# NBMC_SCHEMATIC_wout_709.net
KiCad netlist of a schematic drawn in EAGLE
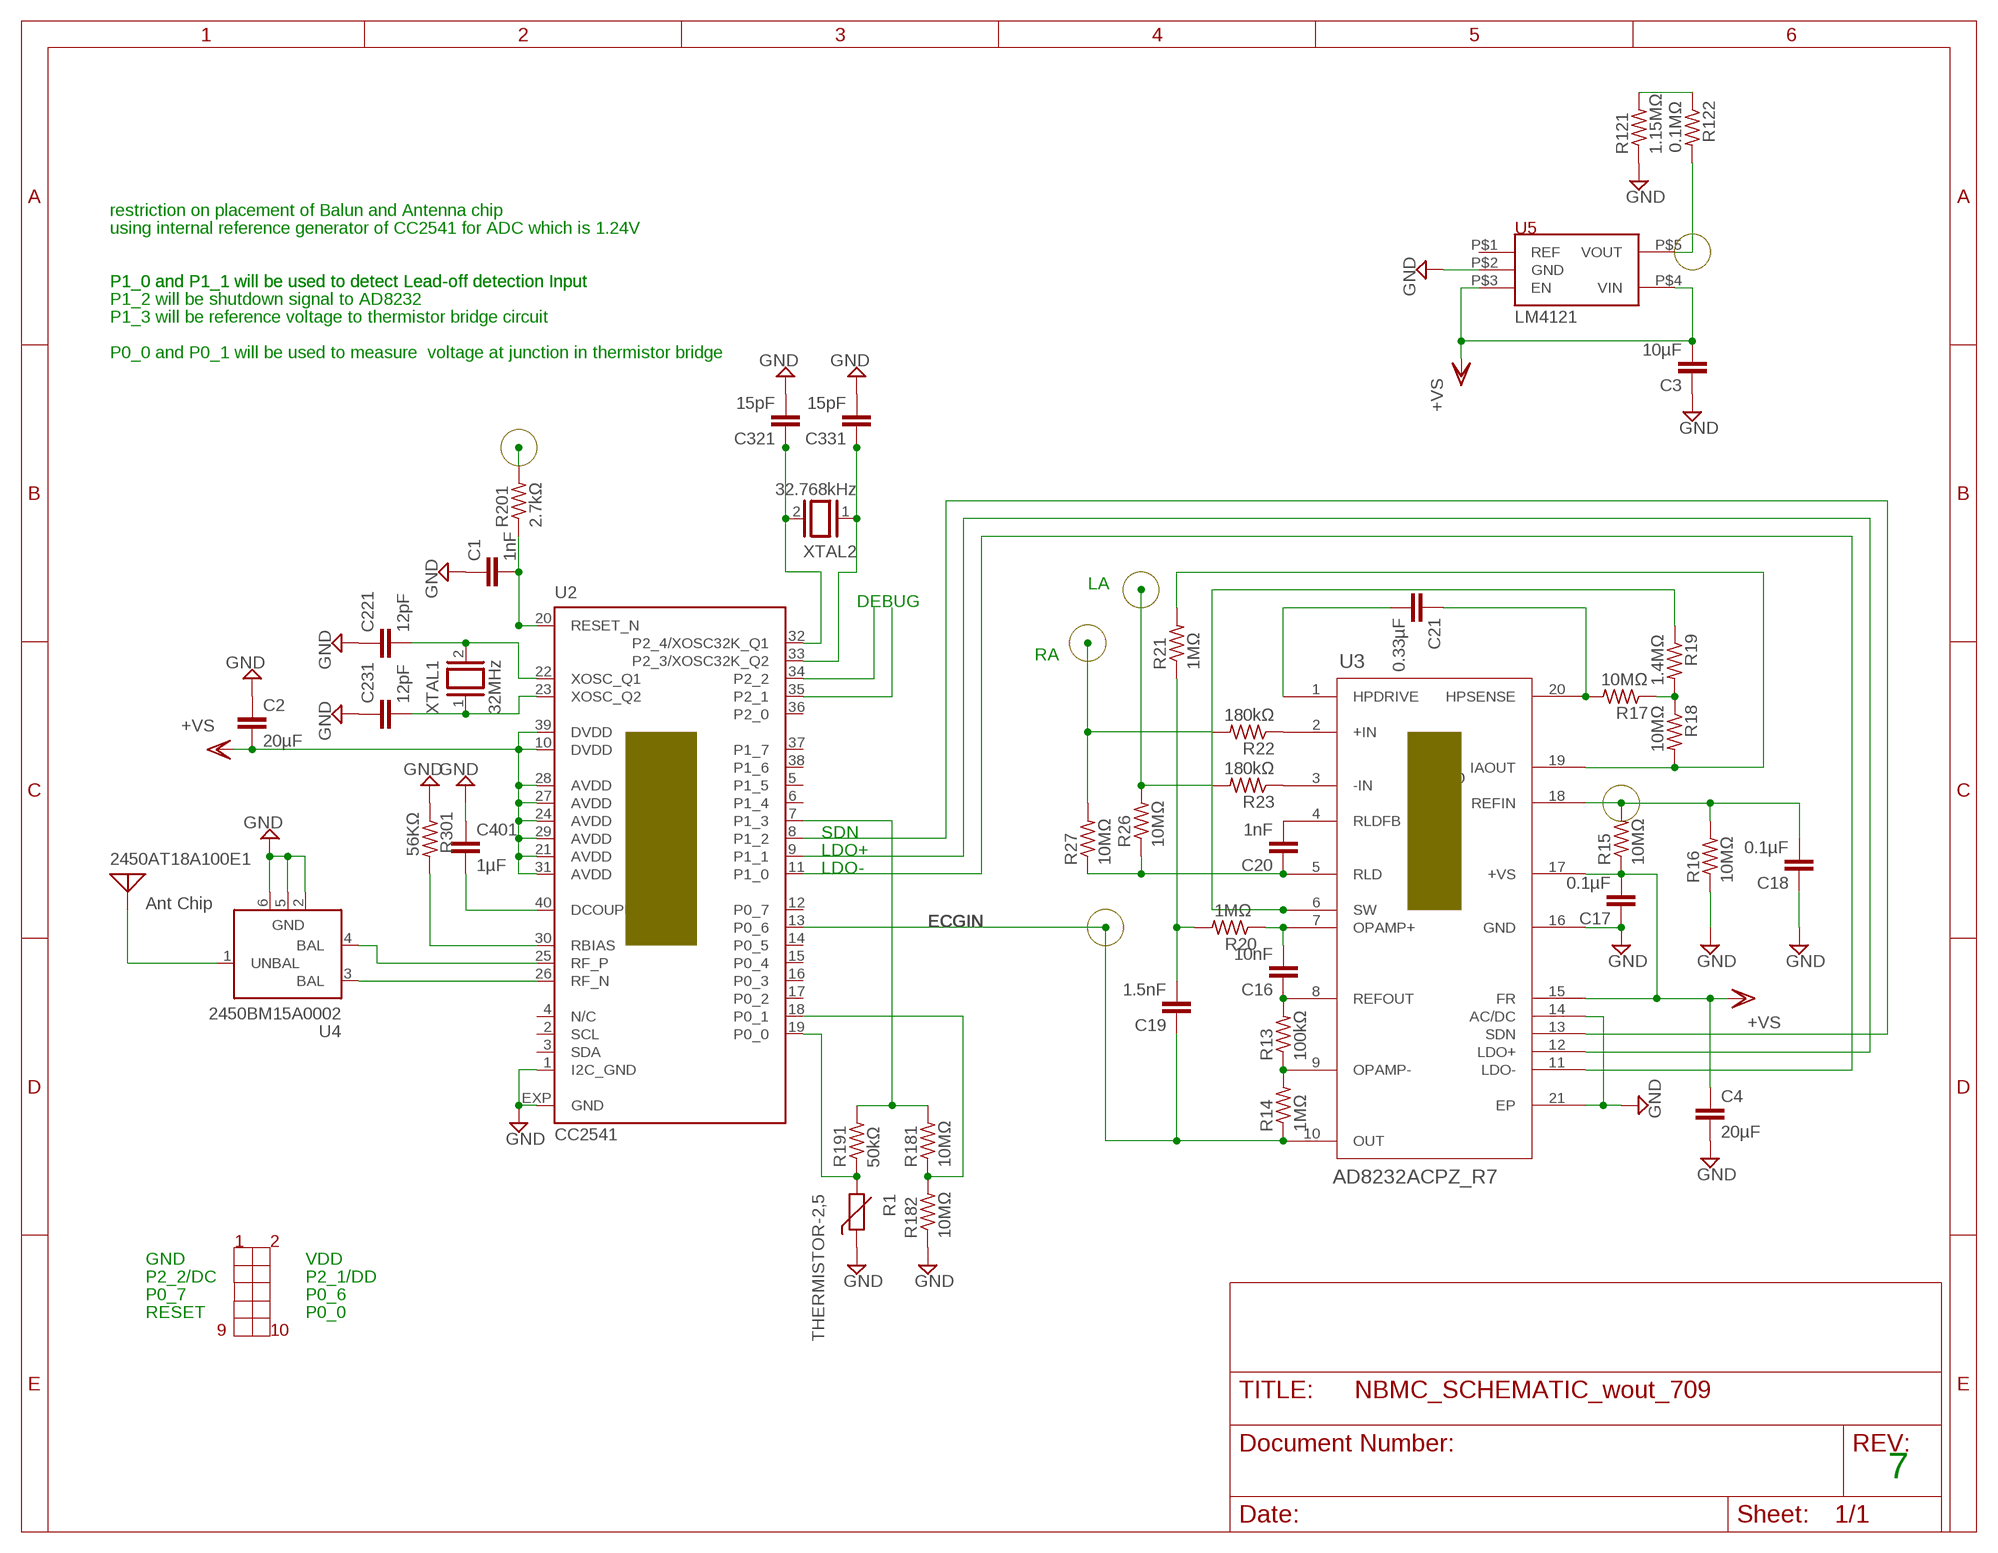
[diagram p0: schematic, sheet 1]

(export (version "E")
  (design (tool "Eeschema 10.0.6"))
  (components
    (comp (ref "2450AT18A100E1")
      (value "Ant Chip")
      (footprint "eagle-import:PAD-01")
      (libsource (lib "eagle-import") (part "ANTENNA"))
    )
    (comp (ref "C1")
      (value "1nF")
      (footprint "eagle-import:C0402")
      (libsource (lib "eagle-import") (part "C-EUC0402"))
    )
    (comp (ref "C2")
      (value "20µF")
      (footprint "eagle-import:C0402")
      (libsource (lib "eagle-import") (part "C-EUC0402"))
    )
    (comp (ref "C3")
      (value "10µF")
      (footprint "eagle-import:C0402")
      (libsource (lib "eagle-import") (part "C-EUC0402"))
    )
    (comp (ref "C4")
      (value "20µF")
      (footprint "eagle-import:C0402")
      (libsource (lib "eagle-import") (part "C-EUC0402"))
    )
    (comp (ref "C16")
      (value "10nF")
      (footprint "eagle-import:C0402")
      (libsource (lib "eagle-import") (part "C-EUC0402"))
    )
    (comp (ref "C17")
      (value "0.1µF")
      (footprint "eagle-import:C0402")
      (libsource (lib "eagle-import") (part "C-EUC0402"))
    )
    (comp (ref "C18")
      (value "0.1µF")
      (footprint "eagle-import:C0402")
      (libsource (lib "eagle-import") (part "C-EUC0402"))
    )
    (comp (ref "C19")
      (value "1.5nF")
      (footprint "eagle-import:C0402")
      (libsource (lib "eagle-import") (part "C-EUC0402"))
    )
    (comp (ref "C20")
      (value "1nF")
      (footprint "eagle-import:C0402")
      (libsource (lib "eagle-import") (part "C-EUC0402"))
    )
    (comp (ref "C21")
      (value "0.33µF")
      (footprint "eagle-import:C0402")
      (libsource (lib "eagle-import") (part "C-EUC0402"))
    )
    (comp (ref "C221")
      (value "12pF")
      (footprint "eagle-import:C0402")
      (libsource (lib "eagle-import") (part "C-EUC0402"))
    )
    (comp (ref "C231")
      (value "12pF")
      (footprint "eagle-import:C0402")
      (libsource (lib "eagle-import") (part "C-EUC0402"))
    )
    (comp (ref "C321")
      (value "15pF")
      (footprint "eagle-import:C0402")
      (libsource (lib "eagle-import") (part "C-EUC0402"))
    )
    (comp (ref "C331")
      (value "15pF")
      (footprint "eagle-import:C0402")
      (libsource (lib "eagle-import") (part "C-EUC0402"))
    )
    (comp (ref "C401")
      (value "1µF")
      (footprint "eagle-import:C0402")
      (libsource (lib "eagle-import") (part "C-EUC0402"))
    )
    (comp (ref "R1")
      (value "THERMISTOR-2,5")
      (footprint "eagle-import:RS-2,5")
      (libsource (lib "eagle-import") (part "THERMISTOR-2,5"))
    )
    (comp (ref "R13")
      (value "100kΩ")
      (footprint "eagle-import:R0402")
      (libsource (lib "eagle-import") (part "R-US_R0402"))
    )
    (comp (ref "R14")
      (value "1MΩ")
      (footprint "eagle-import:R0402")
      (libsource (lib "eagle-import") (part "R-US_R0402"))
    )
    (comp (ref "R15")
      (value "10MΩ")
      (footprint "eagle-import:R0402")
      (libsource (lib "eagle-import") (part "R-US_R0402"))
    )
    (comp (ref "R16")
      (value "10MΩ")
      (footprint "eagle-import:R0402")
      (libsource (lib "eagle-import") (part "R-US_R0402"))
    )
    (comp (ref "R17")
      (value "10MΩ")
      (footprint "eagle-import:R0402")
      (libsource (lib "eagle-import") (part "R-US_R0402"))
    )
    (comp (ref "R18")
      (value "10MΩ")
      (footprint "eagle-import:R0402")
      (libsource (lib "eagle-import") (part "R-US_R0402"))
    )
    (comp (ref "R19")
      (value "1.4MΩ")
      (footprint "eagle-import:R0402")
      (libsource (lib "eagle-import") (part "R-US_R0402"))
    )
    (comp (ref "R20")
      (value "1MΩ")
      (footprint "eagle-import:R0402")
      (libsource (lib "eagle-import") (part "R-US_R0402"))
    )
    (comp (ref "R21")
      (value "1MΩ")
      (footprint "eagle-import:R0402")
      (libsource (lib "eagle-import") (part "R-US_R0402"))
    )
    (comp (ref "R22")
      (value "180kΩ")
      (footprint "eagle-import:R0402")
      (libsource (lib "eagle-import") (part "R-US_R0402"))
    )
    (comp (ref "R23")
      (value "180kΩ")
      (footprint "eagle-import:R0402")
      (libsource (lib "eagle-import") (part "R-US_R0402"))
    )
    (comp (ref "R26")
      (value "10MΩ")
      (footprint "eagle-import:R0402")
      (libsource (lib "eagle-import") (part "R-US_R0402"))
    )
    (comp (ref "R27")
      (value "10MΩ")
      (footprint "eagle-import:R0402")
      (libsource (lib "eagle-import") (part "R-US_R0402"))
    )
    (comp (ref "R121")
      (value "1.15MΩ")
      (footprint "eagle-import:R0402")
      (libsource (lib "eagle-import") (part "R-US_R0402"))
    )
    (comp (ref "R122")
      (value "0.1MΩ")
      (footprint "eagle-import:R0402")
      (libsource (lib "eagle-import") (part "R-US_R0402"))
    )
    (comp (ref "R181")
      (value "10MΩ")
      (footprint "eagle-import:R0402")
      (libsource (lib "eagle-import") (part "R-US_R0402"))
    )
    (comp (ref "R182")
      (value "10MΩ")
      (footprint "eagle-import:R0402")
      (libsource (lib "eagle-import") (part "R-US_R0402"))
    )
    (comp (ref "R191")
      (value "50kΩ")
      (footprint "eagle-import:R0402")
      (libsource (lib "eagle-import") (part "R-US_R0402"))
    )
    (comp (ref "R201")
      (value "2.7kΩ")
      (footprint "eagle-import:R0402")
      (libsource (lib "eagle-import") (part "R-US_R0402"))
    )
    (comp (ref "R301")
      (value "56KΩ")
      (footprint "eagle-import:R0402")
      (libsource (lib "eagle-import") (part "R-US_R0402"))
    )
    (comp (ref "U2")
      (value "CC2541")
      (footprint "eagle-import:RHA_S-PVQFN-N40")
      (libsource (lib "eagle-import") (part "CC2541"))
    )
    (comp (ref "U3")
      (value "AD8232ACPZ_R7")
      (footprint "eagle-import:CP_20_10")
      (libsource (lib "eagle-import") (part "AD8232ACPZ_R7"))
    )
    (comp (ref "U4")
      (value "2450BM15A0002")
      (footprint "eagle-import:2450BM15A0002")
      (libsource (lib "eagle-import") (part "2450BM15A0002"))
    )
    (comp (ref "U5")
      (value "LM4121")
      (footprint "eagle-import:0402")
      (libsource (lib "eagle-import") (part "LM4121"))
    )
    (comp (ref "XTAL1")
      (value "32MHz")
      (footprint "eagle-import:Q")
      (libsource (lib "eagle-import") (part "XTAL"))
    )
    (comp (ref "XTAL2")
      (value "32.768kHz")
      (footprint "eagle-import:Q")
      (libsource (lib "eagle-import") (part "XTAL"))
    )
  )
  (nets
    (net (code "1") (name "+VS") (class "Default")
      (node (ref "C17") (pin "2") (pinfunction "2_2") (pintype "passive"))
      (node (ref "C2") (pin "2") (pinfunction "2_2") (pintype "passive"))
      (node (ref "C3") (pin "2") (pinfunction "2_2") (pintype "passive"))
      (node (ref "C4") (pin "1") (pinfunction "1_1") (pintype "passive"))
      (node (ref "R15") (pin "1") (pinfunction "1_1") (pintype "passive"))
      (node (ref "U2") (pin "10") (pinfunction "DVDD_10") (pintype "power_in"))
      (node (ref "U2") (pin "21") (pinfunction "AVDD_21") (pintype "power_in"))
      (node (ref "U2") (pin "24") (pinfunction "AVDD_24") (pintype "power_in"))
      (node (ref "U2") (pin "27") (pinfunction "AVDD_27") (pintype "power_in"))
      (node (ref "U2") (pin "28") (pinfunction "AVDD_28") (pintype "power_in"))
      (node (ref "U2") (pin "29") (pinfunction "AVDD_29") (pintype "power_in"))
      (node (ref "U2") (pin "31") (pinfunction "AVDD_31") (pintype "power_in"))
      (node (ref "U2") (pin "39") (pinfunction "DVDD_39") (pintype "power_in"))
      (node (ref "U3") (pin "15") (pinfunction "FR_15") (pintype "passive"))
      (node (ref "U3") (pin "17") (pinfunction "+VS_17") (pintype "passive"))
      (node (ref "U5") (pin "P$3") (pinfunction "EN_P$3") (pintype "input"))
      (node (ref "U5") (pin "P$4") (pinfunction "VIN_P$4") (pintype "input"))
    )
    (net (code "2") (name "/ECGIN") (class "Default")
      (node (ref "C19") (pin "1") (pinfunction "1_1") (pintype "passive"))
      (node (ref "R14") (pin "1") (pinfunction "1_1") (pintype "passive"))
      (node (ref "U2") (pin "13") (pinfunction "P0_6_13") (pintype "bidirectional"))
      (node (ref "U3") (pin "10") (pinfunction "OUT_10") (pintype "passive"))
    )
    (net (code "3") (name "/N{slash}C") (class "Default")
      (node (ref "U2") (pin "4") (pinfunction "N/C_4") (pintype "power_in"))
    )
    (net (code "4") (name "GND") (class "Default")
      (node (ref "C1") (pin "1") (pinfunction "1_1") (pintype "passive"))
      (node (ref "C17") (pin "1") (pinfunction "1_1") (pintype "passive"))
      (node (ref "C18") (pin "1") (pinfunction "1_1") (pintype "passive"))
      (node (ref "C2") (pin "1") (pinfunction "1_1") (pintype "passive"))
      (node (ref "C221") (pin "1") (pinfunction "1_1") (pintype "passive"))
      (node (ref "C231") (pin "1") (pinfunction "1_1") (pintype "passive"))
      (node (ref "C3") (pin "1") (pinfunction "1_1") (pintype "passive"))
      (node (ref "C321") (pin "2") (pinfunction "2_2") (pintype "passive"))
      (node (ref "C331") (pin "2") (pinfunction "2_2") (pintype "passive"))
      (node (ref "C4") (pin "2") (pinfunction "2_2") (pintype "passive"))
      (node (ref "C401") (pin "1") (pinfunction "1_1") (pintype "passive"))
      (node (ref "R1") (pin "1") (pinfunction "1_1") (pintype "passive"))
      (node (ref "R121") (pin "1") (pinfunction "1_1") (pintype "passive"))
      (node (ref "R16") (pin "1") (pinfunction "1_1") (pintype "passive"))
      (node (ref "R182") (pin "1") (pinfunction "1_1") (pintype "passive"))
      (node (ref "R301") (pin "1") (pinfunction "1_1") (pintype "passive"))
      (node (ref "U2") (pin "1") (pinfunction "I2C_GND_1") (pintype "power_in"))
      (node (ref "U2") (pin "EXP") (pinfunction "GND_EXP") (pintype "passive"))
      (node (ref "U3") (pin "14") (pinfunction "AC/DC_14") (pintype "passive"))
      (node (ref "U3") (pin "16") (pinfunction "GND_16") (pintype "passive"))
      (node (ref "U3") (pin "21") (pinfunction "EP_21") (pintype "passive"))
      (node (ref "U4") (pin "2") (pinfunction "GND_2") (pintype "passive"))
      (node (ref "U4") (pin "5") (pinfunction "GND_5") (pintype "passive"))
      (node (ref "U4") (pin "6") (pinfunction "GND_6") (pintype "passive"))
      (node (ref "U5") (pin "P$2") (pinfunction "GND_P$2") (pintype "bidirectional"))
    )
    (net (code "5") (name "Net-(C19-Pad2)") (class "Default")
      (node (ref "C19") (pin "2") (pinfunction "2_2") (pintype "passive"))
      (node (ref "R20") (pin "2") (pinfunction "2_2") (pintype "passive"))
      (node (ref "R21") (pin "1") (pinfunction "1_1") (pintype "passive"))
    )
    (net (code "6") (name "Net-(R17-Pad1)") (class "Default")
      (node (ref "R17") (pin "1") (pinfunction "1_1") (pintype "passive"))
      (node (ref "R18") (pin "1") (pinfunction "1_1") (pintype "passive"))
      (node (ref "R19") (pin "2") (pinfunction "2_2") (pintype "passive"))
    )
    (net (code "7") (name "Net-(R22-Pad2)") (class "Default")
      (node (ref "R22") (pin "2") (pinfunction "2_2") (pintype "passive"))
      (node (ref "R27") (pin "2") (pinfunction "2_2") (pintype "passive"))
    )
    (net (code "8") (name "Net-(R23-Pad2)") (class "Default")
      (node (ref "R23") (pin "2") (pinfunction "2_2") (pintype "passive"))
      (node (ref "R26") (pin "2") (pinfunction "2_2") (pintype "passive"))
    )
    (net (code "9") (name "Net-(R121-Pad2)") (class "Default")
      (node (ref "R121") (pin "2") (pinfunction "2_2") (pintype "passive"))
      (node (ref "R122") (pin "1") (pinfunction "1_1") (pintype "passive"))
    )
    (net (code "10") (name "Net-(U2-DCOUPL)") (class "Default")
      (node (ref "C401") (pin "2") (pinfunction "2_2") (pintype "passive"))
      (node (ref "U2") (pin "40") (pinfunction "DCOUPL_40") (pintype "power_in"))
    )
    (net (code "11") (name "Net-(U2-P0_0)") (class "Default")
      (node (ref "R1") (pin "2") (pinfunction "2_2") (pintype "passive"))
      (node (ref "R191") (pin "1") (pinfunction "1_1") (pintype "passive"))
      (node (ref "U2") (pin "19") (pinfunction "P0_0_19") (pintype "bidirectional"))
    )
    (net (code "12") (name "Net-(U2-P0_1)") (class "Default")
      (node (ref "R181") (pin "1") (pinfunction "1_1") (pintype "passive"))
      (node (ref "R182") (pin "2") (pinfunction "2_2") (pintype "passive"))
      (node (ref "U2") (pin "18") (pinfunction "P0_1_18") (pintype "bidirectional"))
    )
    (net (code "13") (name "Net-(U2-P1_0)") (class "Default")
      (node (ref "U2") (pin "11") (pinfunction "P1_0_11") (pintype "bidirectional"))
      (node (ref "U3") (pin "11") (pinfunction "LDO-_11") (pintype "passive"))
    )
    (net (code "14") (name "Net-(U2-P1_1)") (class "Default")
      (node (ref "U2") (pin "9") (pinfunction "P1_1_9") (pintype "bidirectional"))
      (node (ref "U3") (pin "12") (pinfunction "LDO+_12") (pintype "passive"))
    )
    (net (code "15") (name "Net-(U2-P1_2)") (class "Default")
      (node (ref "U2") (pin "8") (pinfunction "P1_2_8") (pintype "bidirectional"))
      (node (ref "U3") (pin "13") (pinfunction "SDN_13") (pintype "passive"))
    )
    (net (code "16") (name "Net-(U2-P1_3)") (class "Default")
      (node (ref "R181") (pin "2") (pinfunction "2_2") (pintype "passive"))
      (node (ref "R191") (pin "2") (pinfunction "2_2") (pintype "passive"))
      (node (ref "U2") (pin "7") (pinfunction "P1_3_7") (pintype "bidirectional"))
    )
    (net (code "17") (name "Net-(U2-P2_3{slash}XOSC32K_Q2)") (class "Default")
      (node (ref "C331") (pin "1") (pinfunction "1_1") (pintype "passive"))
      (node (ref "U2") (pin "33") (pinfunction "P2_3/XOSC32K_Q2_33") (pintype "bidirectional"))
      (node (ref "XTAL2") (pin "1") (pinfunction "1_1") (pintype "passive"))
    )
    (net (code "18") (name "Net-(U2-P2_4{slash}XOSC32K_Q1)") (class "Default")
      (node (ref "C321") (pin "1") (pinfunction "1_1") (pintype "passive"))
      (node (ref "U2") (pin "32") (pinfunction "P2_4/XOSC32K_Q1_32") (pintype "bidirectional"))
      (node (ref "XTAL2") (pin "2") (pinfunction "2_2") (pintype "passive"))
    )
    (net (code "19") (name "Net-(U2-RBIAS)") (class "Default")
      (node (ref "R301") (pin "2") (pinfunction "2_2") (pintype "passive"))
      (node (ref "U2") (pin "30") (pinfunction "RBIAS_30") (pintype "bidirectional"))
    )
    (net (code "20") (name "Net-(U2-RESET_N)") (class "Default")
      (node (ref "C1") (pin "2") (pinfunction "2_2") (pintype "passive"))
      (node (ref "R201") (pin "1") (pinfunction "1_1") (pintype "passive"))
      (node (ref "U2") (pin "20") (pinfunction "RESET_N_20") (pintype "input"))
    )
    (net (code "21") (name "Net-(U2-RF_N)") (class "Default")
      (node (ref "U2") (pin "26") (pinfunction "RF_N_26") (pintype "bidirectional"))
      (node (ref "U4") (pin "3") (pinfunction "BAL_3") (pintype "passive"))
    )
    (net (code "22") (name "Net-(U2-RF_P)") (class "Default")
      (node (ref "U2") (pin "25") (pinfunction "RF_P_25") (pintype "bidirectional"))
      (node (ref "U4") (pin "4") (pinfunction "BAL_4") (pintype "passive"))
    )
    (net (code "23") (name "Net-(U2-XOSC_Q1)") (class "Default")
      (node (ref "C221") (pin "2") (pinfunction "2_2") (pintype "passive"))
      (node (ref "U2") (pin "22") (pinfunction "XOSC_Q1_22") (pintype "bidirectional"))
      (node (ref "XTAL1") (pin "2") (pinfunction "2_2") (pintype "passive"))
    )
    (net (code "24") (name "Net-(U2-XOSC_Q2)") (class "Default")
      (node (ref "C231") (pin "2") (pinfunction "2_2") (pintype "passive"))
      (node (ref "U2") (pin "23") (pinfunction "XOSC_Q2_23") (pintype "bidirectional"))
      (node (ref "XTAL1") (pin "1") (pinfunction "1_1") (pintype "passive"))
    )
    (net (code "25") (name "Net-(U3-+IN)") (class "Default")
      (node (ref "R22") (pin "1") (pinfunction "1_1") (pintype "passive"))
      (node (ref "U3") (pin "2") (pinfunction "+IN_2") (pintype "passive"))
    )
    (net (code "26") (name "Net-(U3--IN)") (class "Default")
      (node (ref "R23") (pin "1") (pinfunction "1_1") (pintype "passive"))
      (node (ref "U3") (pin "3") (pinfunction "-IN_3") (pintype "passive"))
    )
    (net (code "27") (name "Net-(U3-HPDRIVE)") (class "Default")
      (node (ref "C21") (pin "2") (pinfunction "2_2") (pintype "passive"))
      (node (ref "U3") (pin "1") (pinfunction "HPDRIVE_1") (pintype "passive"))
    )
    (net (code "28") (name "Net-(U3-HPSENSE)") (class "Default")
      (node (ref "C21") (pin "1") (pinfunction "1_1") (pintype "passive"))
      (node (ref "R17") (pin "2") (pinfunction "2_2") (pintype "passive"))
      (node (ref "U3") (pin "20") (pinfunction "HPSENSE_20") (pintype "passive"))
    )
    (net (code "29") (name "Net-(U3-IAOUT)") (class "Default")
      (node (ref "R18") (pin "2") (pinfunction "2_2") (pintype "passive"))
      (node (ref "R21") (pin "2") (pinfunction "2_2") (pintype "passive"))
      (node (ref "U3") (pin "19") (pinfunction "IAOUT_19") (pintype "passive"))
    )
    (net (code "30") (name "Net-(U3-OPAMP+)") (class "Default")
      (node (ref "C16") (pin "2") (pinfunction "2_2") (pintype "passive"))
      (node (ref "R20") (pin "1") (pinfunction "1_1") (pintype "passive"))
      (node (ref "U3") (pin "7") (pinfunction "OPAMP+_7") (pintype "passive"))
    )
    (net (code "31") (name "Net-(U3-OPAMP-)") (class "Default")
      (node (ref "R13") (pin "1") (pinfunction "1_1") (pintype "passive"))
      (node (ref "R14") (pin "2") (pinfunction "2_2") (pintype "passive"))
      (node (ref "U3") (pin "9") (pinfunction "OPAMP-_9") (pintype "passive"))
    )
    (net (code "32") (name "Net-(U3-REFIN)") (class "Default")
      (node (ref "C18") (pin "2") (pinfunction "2_2") (pintype "passive"))
      (node (ref "R15") (pin "2") (pinfunction "2_2") (pintype "passive"))
      (node (ref "R16") (pin "2") (pinfunction "2_2") (pintype "passive"))
      (node (ref "U3") (pin "18") (pinfunction "REFIN_18") (pintype "passive"))
    )
    (net (code "33") (name "Net-(U3-REFOUT)") (class "Default")
      (node (ref "C16") (pin "1") (pinfunction "1_1") (pintype "passive"))
      (node (ref "R13") (pin "2") (pinfunction "2_2") (pintype "passive"))
      (node (ref "U3") (pin "8") (pinfunction "REFOUT_8") (pintype "passive"))
    )
    (net (code "34") (name "Net-(U3-RLD)") (class "Default")
      (node (ref "C20") (pin "1") (pinfunction "1_1") (pintype "passive"))
      (node (ref "R26") (pin "1") (pinfunction "1_1") (pintype "passive"))
      (node (ref "R27") (pin "1") (pinfunction "1_1") (pintype "passive"))
      (node (ref "U3") (pin "5") (pinfunction "RLD_5") (pintype "passive"))
    )
    (net (code "35") (name "Net-(U3-RLDFB)") (class "Default")
      (node (ref "C20") (pin "2") (pinfunction "2_2") (pintype "passive"))
      (node (ref "U3") (pin "4") (pinfunction "RLDFB_4") (pintype "passive"))
    )
    (net (code "36") (name "Net-(U3-SW)") (class "Default")
      (node (ref "R19") (pin "1") (pinfunction "1_1") (pintype "passive"))
      (node (ref "U3") (pin "6") (pinfunction "SW_6") (pintype "passive"))
    )
    (net (code "37") (name "Net-(U4-UNBAL)") (class "Default")
      (node (ref "2450AT18A100E1") (pin "1") (pinfunction "1_1") (pintype "output"))
      (node (ref "U4") (pin "1") (pinfunction "UNBAL_1") (pintype "passive"))
    )
    (net (code "38") (name "Net-(U5-VOUT)") (class "Default")
      (node (ref "R122") (pin "2") (pinfunction "2_2") (pintype "passive"))
      (node (ref "U5") (pin "P$5") (pinfunction "VOUT_P$5") (pintype "output"))
    )
    (net (code "39") (name "unconnected-(R201-Pad2)") (class "Default")
      (node (ref "R201") (pin "2") (pinfunction "2_2") (pintype "passive"))
    )
    (net (code "40") (name "unconnected-(U2-P0_2-Pad17)") (class "Default")
      (node (ref "U2") (pin "17") (pinfunction "P0_2_17") (pintype "bidirectional"))
    )
    (net (code "41") (name "unconnected-(U2-P0_3-Pad16)") (class "Default")
      (node (ref "U2") (pin "16") (pinfunction "P0_3_16") (pintype "bidirectional"))
    )
    (net (code "42") (name "unconnected-(U2-P0_4-Pad15)") (class "Default")
      (node (ref "U2") (pin "15") (pinfunction "P0_4_15") (pintype "bidirectional"))
    )
    (net (code "43") (name "unconnected-(U2-P0_5-Pad14)") (class "Default")
      (node (ref "U2") (pin "14") (pinfunction "P0_5_14") (pintype "bidirectional"))
    )
    (net (code "44") (name "unconnected-(U2-P0_7-Pad12)") (class "Default")
      (node (ref "U2") (pin "12") (pinfunction "P0_7_12") (pintype "bidirectional"))
    )
    (net (code "45") (name "unconnected-(U2-P1_4-Pad6)") (class "Default")
      (node (ref "U2") (pin "6") (pinfunction "P1_4_6") (pintype "bidirectional"))
    )
    (net (code "46") (name "unconnected-(U2-P1_5-Pad5)") (class "Default")
      (node (ref "U2") (pin "5") (pinfunction "P1_5_5") (pintype "bidirectional"))
    )
    (net (code "47") (name "unconnected-(U2-P1_6-Pad38)") (class "Default")
      (node (ref "U2") (pin "38") (pinfunction "P1_6_38") (pintype "bidirectional"))
    )
    (net (code "48") (name "unconnected-(U2-P1_7-Pad37)") (class "Default")
      (node (ref "U2") (pin "37") (pinfunction "P1_7_37") (pintype "bidirectional"))
    )
    (net (code "49") (name "unconnected-(U2-P2_0-Pad36)") (class "Default")
      (node (ref "U2") (pin "36") (pinfunction "P2_0_36") (pintype "bidirectional"))
    )
    (net (code "50") (name "unconnected-(U2-P2_1-Pad35)") (class "Default")
      (node (ref "U2") (pin "35") (pinfunction "P2_1_35") (pintype "bidirectional"))
    )
    (net (code "51") (name "unconnected-(U2-P2_2-Pad34)") (class "Default")
      (node (ref "U2") (pin "34") (pinfunction "P2_2_34") (pintype "bidirectional"))
    )
    (net (code "52") (name "unconnected-(U2-SCL-Pad2)") (class "Default")
      (node (ref "U2") (pin "2") (pinfunction "SCL_2") (pintype "bidirectional"))
    )
    (net (code "53") (name "unconnected-(U2-SDA-Pad3)") (class "Default")
      (node (ref "U2") (pin "3") (pinfunction "SDA_3") (pintype "bidirectional"))
    )
    (net (code "54") (name "unconnected-(U5-REF-PadP$1)") (class "Default")
      (node (ref "U5") (pin "P$1") (pinfunction "REF_P$1") (pintype "bidirectional"))
    )
  )
)
